# Power1.net
KiCad netlist of a schematic drawn in Altium Designer
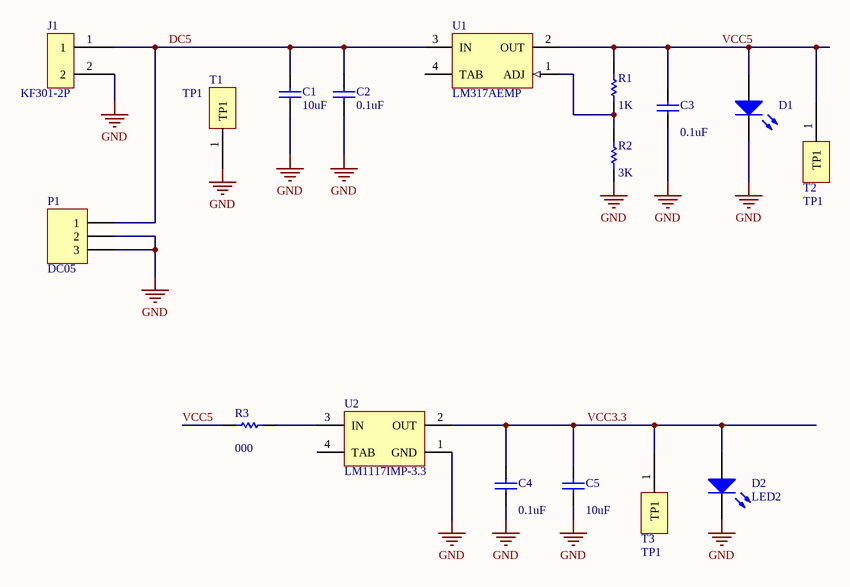
[diagram p0: Power1.SchDoc]

(export (version "E")
  (design (tool "Eeschema 10.0.6"))
  (components
    (comp (ref "C1")
      (value "10uF")
      (footprint "CAPC3216L")
      (description "Capacitor (Semiconductor SIM Model)")
      (fields (field (name "Comment") "Cap Semi") (field (name "PUBLISHER") "Altium Limited"))
      (libsource (lib "Miscellaneous Devices") (part "Cap Semi"))
    )
    (comp (ref "C2")
      (value "0.1uF")
      (footprint "CAPC3216L")
      (description "Capacitor (Semiconductor SIM Model)")
      (fields (field (name "Comment") "Cap Semi") (field (name "PUBLISHER") "Altium Limited"))
      (libsource (lib "Miscellaneous Devices") (part "Cap Semi"))
    )
    (comp (ref "C3")
      (value "0.1uF")
      (footprint "CAPC3216L")
      (description "Capacitor (Semiconductor SIM Model)")
      (fields (field (name "Comment") "Cap Semi") (field (name "PUBLISHER") "Altium Limited"))
      (libsource (lib "Miscellaneous Devices") (part "Cap Semi"))
    )
    (comp (ref "C4")
      (value "0.1uF")
      (footprint "CAPC3216L")
      (description "Capacitor (Semiconductor SIM Model)")
      (fields (field (name "Comment") "Cap Semi") (field (name "PUBLISHER") "Altium Limited"))
      (libsource (lib "Miscellaneous Devices") (part "Cap Semi"))
    )
    (comp (ref "C5")
      (value "10uF")
      (footprint "CAPC3216L")
      (description "Capacitor (Semiconductor SIM Model)")
      (fields (field (name "Comment") "Cap Semi") (field (name "PUBLISHER") "Altium Limited"))
      (libsource (lib "Miscellaneous Devices") (part "Cap Semi"))
    )
    (comp (ref "D1")
      (value "LED0")
      (footprint "CAPC2512L")
      (description "Typical INFRARED GaAs LED")
      (fields (field (name "PUBLISHER") "Altium Limited"))
      (libsource (lib "Miscellaneous Devices") (part "LED0"))
    )
    (comp (ref "D2")
      (value "LED2")
      (footprint "CAPC2512L")
      (description "Typical RED, GREEN, YELLOW, AMBER GaAs LED")
      (fields (field (name "PUBLISHER") "Altium Limited"))
      (libsource (lib "Miscellaneous Devices") (part "LED2"))
    )
    (comp (ref "J1") (value "KF301-2P") (footprint "KF301-2P") (libsource (lib "CHK-I") (part "KF301-2P")))
    (comp (ref "P1")
      (value "DC05")
      (footprint "DC005")
      (description "Header, 3-Pin")
      (fields (field (name "PUBLISHER") "Altium Limited"))
      (libsource (lib "Miscellaneous Connectors") (part "Header 3"))
    )
    (comp (ref "R1")
      (value "1K")
      (footprint "RESC3216L")
      (description "Semiconductor Resistor")
      (fields (field (name "Comment") "Res Semi") (field (name "PUBLISHER") "Altium Limited"))
      (libsource (lib "Miscellaneous Devices") (part "Res Semi"))
    )
    (comp (ref "R2")
      (value "3K")
      (footprint "RESC3216L")
      (description "Semiconductor Resistor")
      (fields (field (name "Comment") "Res Semi") (field (name "PUBLISHER") "Altium Limited"))
      (libsource (lib "Miscellaneous Devices") (part "Res Semi"))
    )
    (comp (ref "R3")
      (value "000")
      (footprint "RESC3216L")
      (description "Semiconductor Resistor")
      (fields (field (name "Comment") "Res Semi") (field (name "PUBLISHER") "Altium Limited"))
      (libsource (lib "Miscellaneous Devices") (part "Res Semi"))
    )
    (comp (ref "T1") (value "TP1") (footprint "TP1") (libsource (lib "") (part "TP1_1")))
    (comp (ref "T2") (value "TP1") (footprint "TP1") (libsource (lib "CHK-I") (part "TP1")))
    (comp (ref "T3") (value "TP1") (footprint "TP1") (libsource (lib "CHK-I") (part "TP1")))
    (comp (ref "U1")
      (value "LM317AEMP")
      (footprint "MP04A_L")
      (description "3-Terminal Adjustable Regulator")
      (fields
        (field (name "MANUFACTURER") "National Semiconductor")
        (field (name "DIGIKEYPARTNUMBER") "LM317AEMPCT-ND")
        (field (name "PUBLISHER") "Altium Limited")
      )
      (libsource (lib "NSC LDO") (part "LM317AEMP"))
    )
    (comp (ref "U2")
      (value "LM1117IMP-3.3")
      (footprint "MP04A_N")
      (description "800mA Low-Dropout Linear Regulator")
      (fields
        (field (name "MANUFACTURER") "National Semiconductor")
        (field (name "DIGIKEYPARTNUMBER") "LM1117IMP-3.3CT-ND")
        (field (name "PUBLISHER") "Altium Limited")
      )
      (libsource (lib "NSC LDO") (part "LM1117IMP-3.3"))
    )
  )
  (nets
    (net (code "1") (name "/DC5") (class "Default")
      (node (ref "C1") (pin "2") (pinfunction "2_2") (pintype "passive"))
      (node (ref "C2") (pin "2") (pinfunction "2_2") (pintype "passive"))
      (node (ref "J1") (pin "1") (pinfunction "1_1") (pintype "passive"))
      (node (ref "P1") (pin "1") (pinfunction "1_1") (pintype "passive"))
      (node (ref "U1") (pin "3") (pinfunction "IN_3") (pintype "power_in"))
    )
    (net (code "2") (name "/VCC3.3") (class "Default")
      (node (ref "C4") (pin "2") (pinfunction "2_2") (pintype "passive"))
      (node (ref "C5") (pin "2") (pinfunction "2_2") (pintype "passive"))
      (node (ref "D2") (pin "1") (pinfunction "A_1") (pintype "passive"))
      (node (ref "T3") (pin "1") (pinfunction "TP1_1") (pintype "passive"))
      (node (ref "U2") (pin "2") (pinfunction "OUT_2") (pintype "power_in"))
    )
    (net (code "3") (name "/VCC5") (class "Default")
      (node (ref "C3") (pin "2") (pinfunction "2_2") (pintype "passive"))
      (node (ref "D1") (pin "1") (pinfunction "A_1") (pintype "passive"))
      (node (ref "R1") (pin "2") (pinfunction "2_2") (pintype "passive"))
      (node (ref "R3") (pin "1") (pinfunction "1_1") (pintype "passive"))
      (node (ref "T2") (pin "1") (pinfunction "TP1_1") (pintype "passive"))
      (node (ref "U1") (pin "2") (pinfunction "OUT_2") (pintype "power_in"))
    )
    (net (code "4") (name "GND") (class "Default")
      (node (ref "C1") (pin "1") (pinfunction "1_1") (pintype "passive"))
      (node (ref "C2") (pin "1") (pinfunction "1_1") (pintype "passive"))
      (node (ref "C3") (pin "1") (pinfunction "1_1") (pintype "passive"))
      (node (ref "C4") (pin "1") (pinfunction "1_1") (pintype "passive"))
      (node (ref "C5") (pin "1") (pinfunction "1_1") (pintype "passive"))
      (node (ref "D1") (pin "2") (pinfunction "K_2") (pintype "passive"))
      (node (ref "D2") (pin "2") (pinfunction "K_2") (pintype "passive"))
      (node (ref "J1") (pin "2") (pinfunction "2_2") (pintype "passive"))
      (node (ref "P1") (pin "2") (pinfunction "2_2") (pintype "passive"))
      (node (ref "P1") (pin "3") (pinfunction "3_3") (pintype "passive"))
      (node (ref "R2") (pin "1") (pinfunction "1_1") (pintype "passive"))
      (node (ref "T1") (pin "1") (pinfunction "TP1_1") (pintype "passive"))
      (node (ref "U2") (pin "1") (pinfunction "GND_1") (pintype "power_in"))
    )
    (net (code "5") (name "Net-(U1-ADJ)") (class "Default")
      (node (ref "R1") (pin "1") (pinfunction "1_1") (pintype "passive"))
      (node (ref "R2") (pin "2") (pinfunction "2_2") (pintype "passive"))
      (node (ref "U1") (pin "1") (pinfunction "ADJ_1") (pintype "input"))
    )
    (net (code "6") (name "Net-(U2-IN)") (class "Default")
      (node (ref "R3") (pin "2") (pinfunction "2_2") (pintype "passive"))
      (node (ref "U2") (pin "3") (pinfunction "IN_3") (pintype "power_in"))
    )
    (net (code "7") (name "unconnected-(U1-TAB-Pad4)") (class "Default")
      (node (ref "U1") (pin "4") (pinfunction "TAB_4") (pintype "power_in"))
    )
    (net (code "8") (name "unconnected-(U2-TAB-Pad4)") (class "Default")
      (node (ref "U2") (pin "4") (pinfunction "TAB_4") (pintype "power_in"))
    )
  )
)
